# IB_WIFI_V2.net
KiCad netlist of a schematic drawn in EAGLE
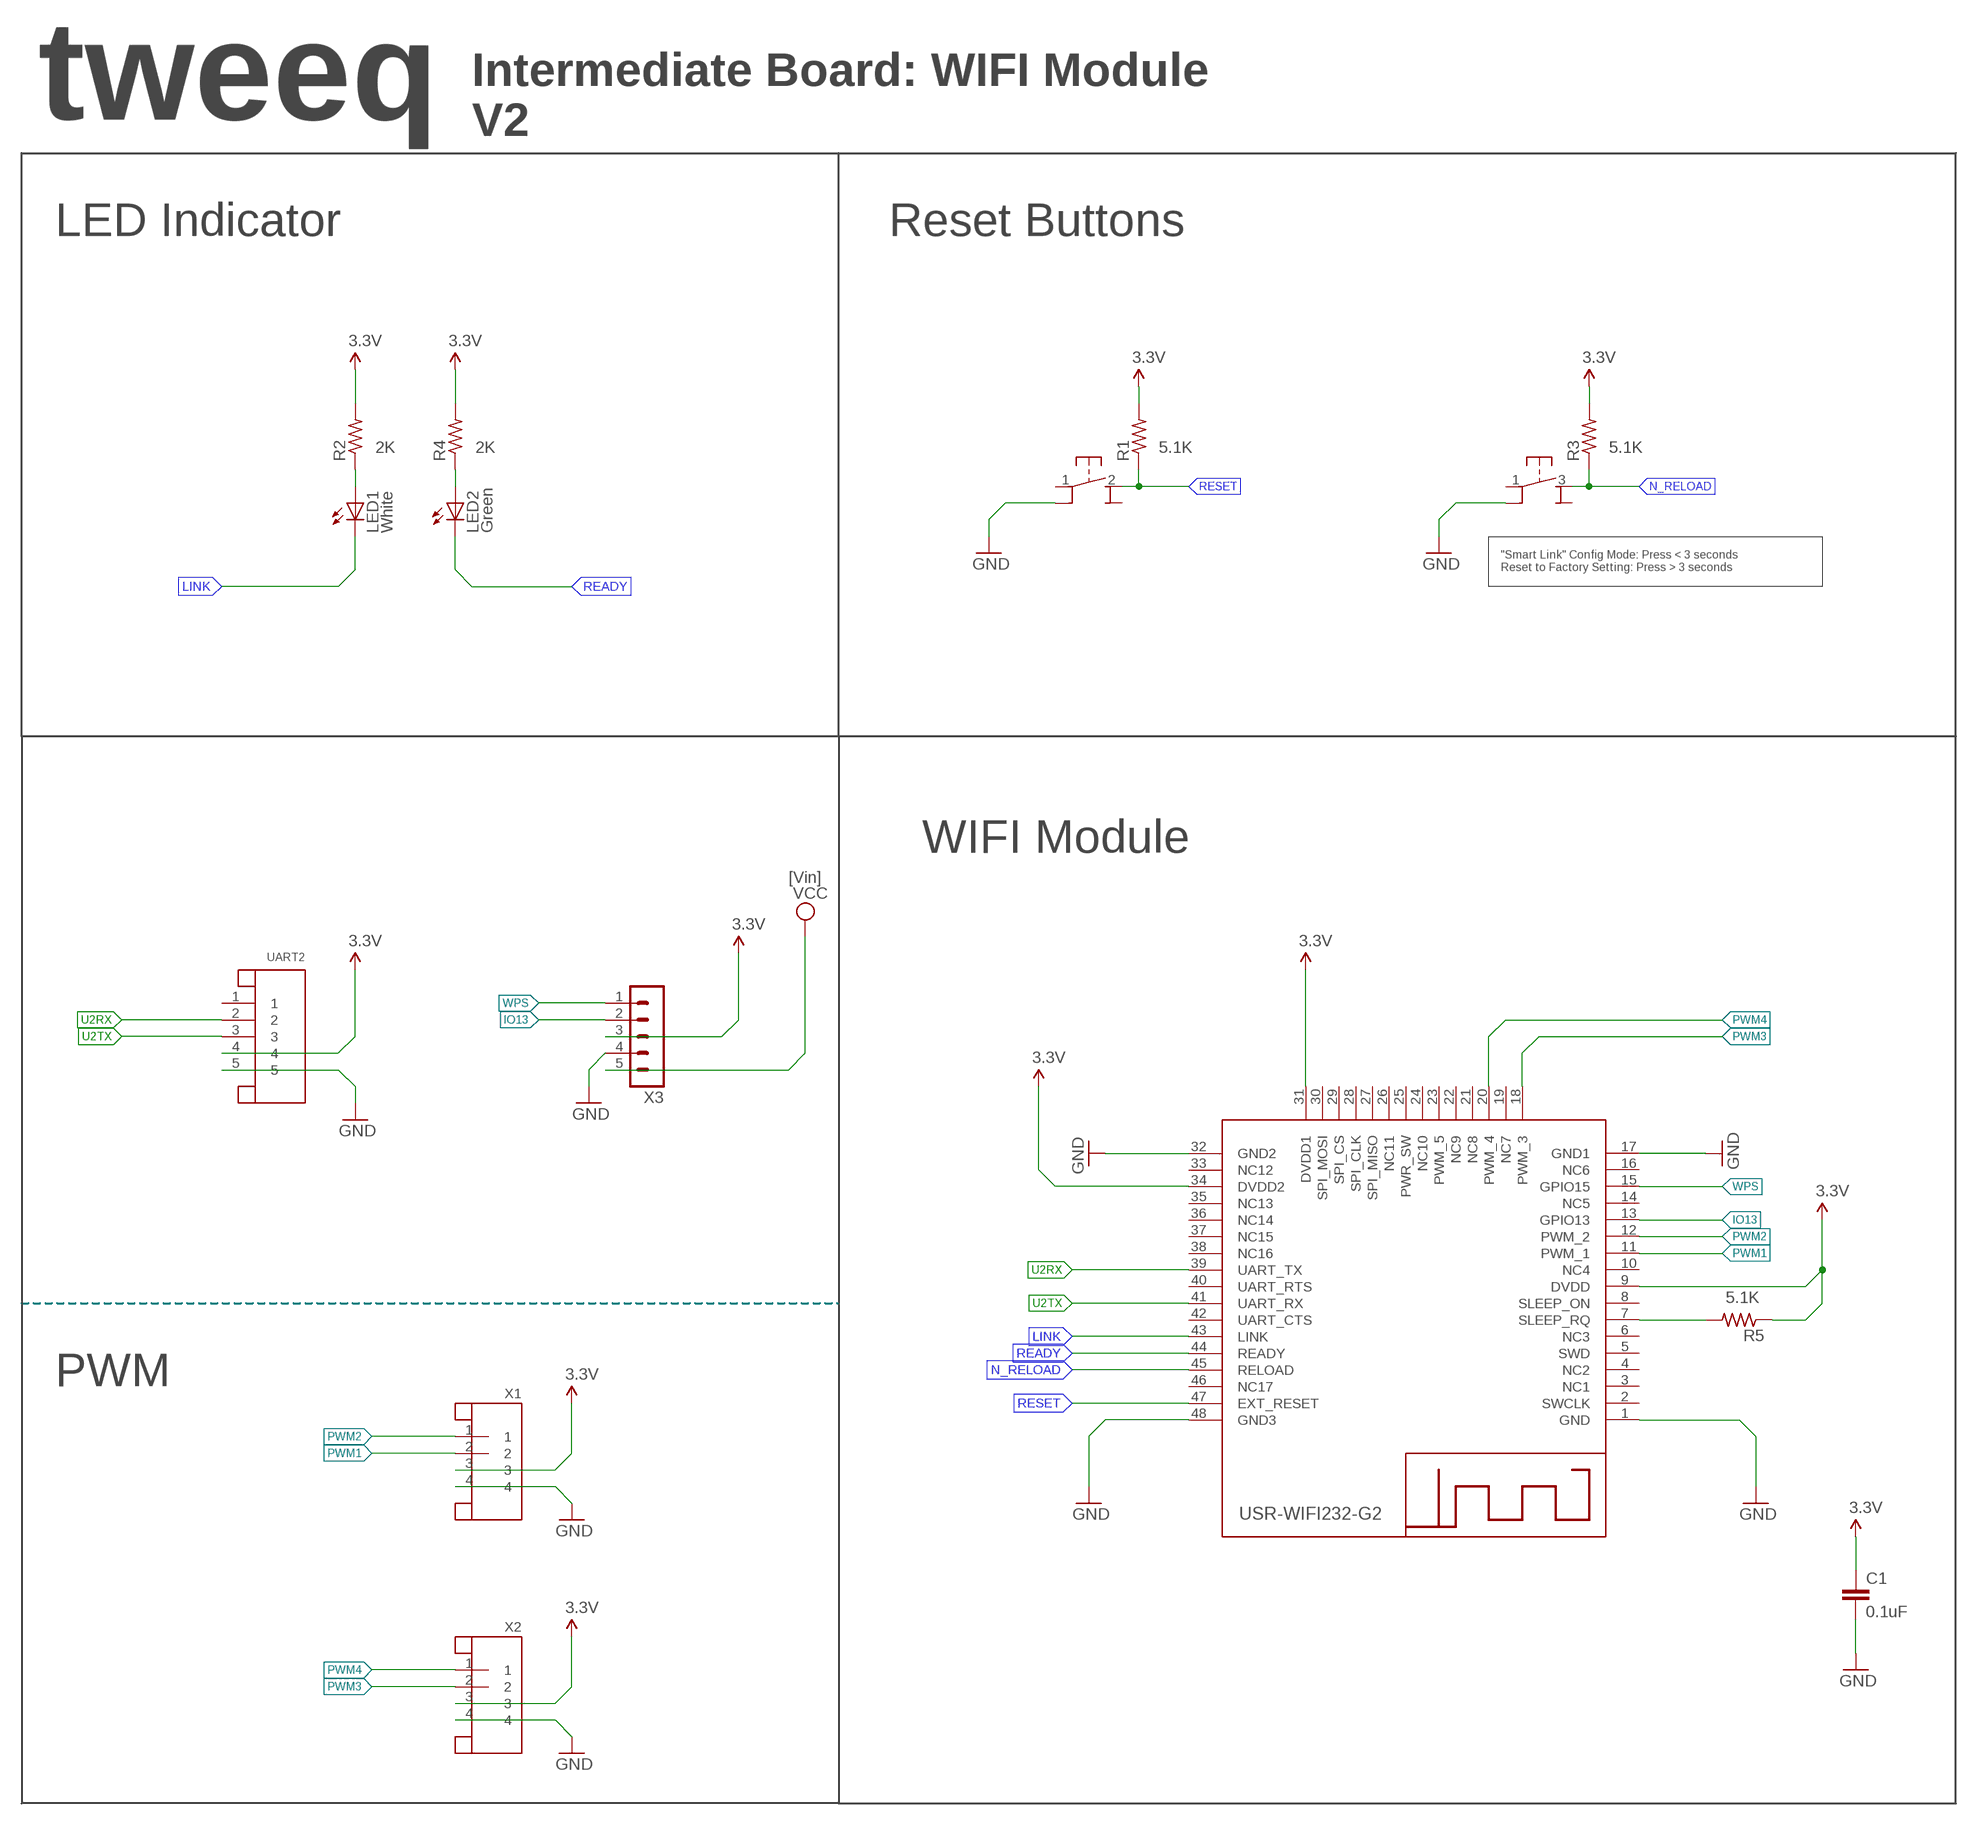
[diagram p0: schematic, sheet 1, part 1 of 2]
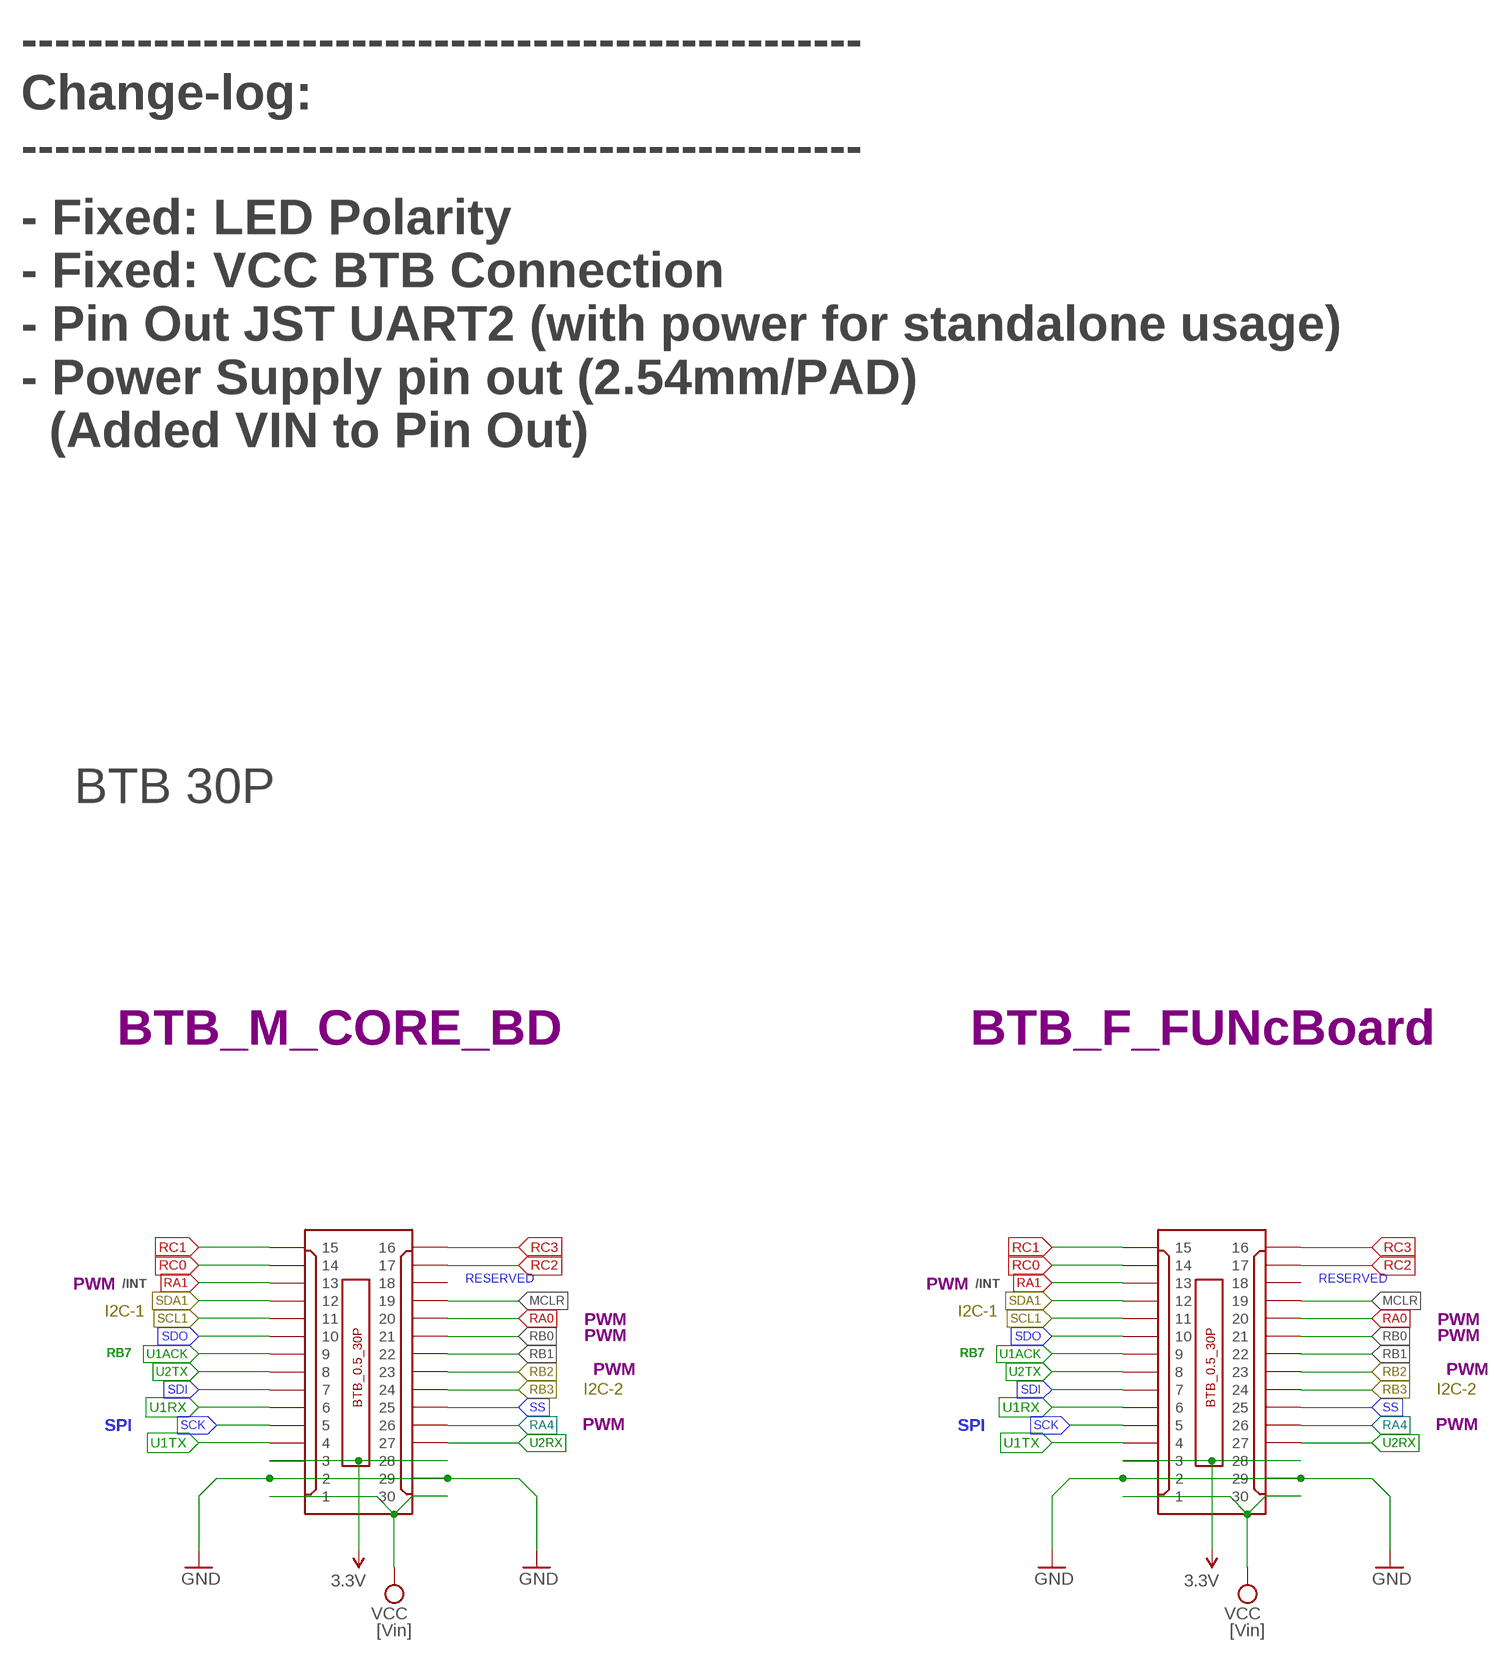
[diagram p1: schematic, sheet 1, part 2 of 2]

(export (version "E")
  (design (tool "Eeschema 10.0.6"))
  (components
    (comp (ref "C1")
      (value "0.1uF")
      (footprint "eagle-import:C0603")
      (libsource (lib "eagle-import") (part "C-EUC0603"))
    )
    (comp (ref "LED1")
      (value "White")
      (footprint "eagle-import:CHIPLED_0805")
      (libsource (lib "eagle-import") (part "LEDCHIPLED_0805"))
    )
    (comp (ref "LED2")
      (value "Green")
      (footprint "eagle-import:CHIPLED_0805")
      (libsource (lib "eagle-import") (part "LEDCHIPLED_0805"))
    )
    (comp (ref "R1")
      (value "5.1K")
      (footprint "eagle-import:R0603")
      (libsource (lib "eagle-import") (part "R-US_R0603"))
    )
    (comp (ref "R2")
      (value "2K")
      (footprint "eagle-import:R0603")
      (libsource (lib "eagle-import") (part "R-US_R0603"))
    )
    (comp (ref "R3")
      (value "5.1K")
      (footprint "eagle-import:R0603")
      (libsource (lib "eagle-import") (part "R-US_R0603"))
    )
    (comp (ref "R4")
      (value "2K")
      (footprint "eagle-import:R0603")
      (libsource (lib "eagle-import") (part "R-US_R0603"))
    )
    (comp (ref "R5")
      (value "5.1K")
      (footprint "eagle-import:R0603")
      (libsource (lib "eagle-import") (part "R-US_R0603"))
    )
    (comp (ref "U$1")
      (value "BTB_CONN_30P/M")
      (footprint "eagle-import:BTB0.5-30M-3.0G")
      (libsource (lib "eagle-import") (part "BTB_CONN_30P/M"))
    )
    (comp (ref "U$3")
      (value "BTB_CONN_30P/F")
      (footprint "eagle-import:BTB0.5-30F-3.0G")
      (libsource (lib "eagle-import") (part "BTB_CONN_30P/F"))
    )
    (comp (ref "U$4")
      (value "PB_MICRO_SMT")
      (footprint "eagle-import:PB_SMT_3.5X3X2")
      (libsource (lib "eagle-import") (part "PB_MICRO_SMT"))
    )
    (comp (ref "U$5")
      (value "PB_MICRO_SMTRIGHTANGLE")
      (footprint "eagle-import:PB_SMT_90D6.2X4.6")
      (libsource (lib "eagle-import") (part "PB_MICRO_SMTRIGHTANGLE"))
    )
    (comp (ref "UART2")
      (value "JST-5PINSH")
      (footprint "eagle-import:SH1.0-5PIN")
      (libsource (lib "eagle-import") (part "JST-5PINSH"))
    )
    (comp (ref "USR-WIFI232-G2")
      (value "USR-WIFI232-G2")
      (footprint "eagle-import:USR-WIFI232-G")
      (libsource (lib "eagle-import") (part "USR-WIFI232-G2"))
    )
    (comp (ref "X1")
      (value "JST-4PINSH")
      (footprint "eagle-import:SH1.0-4PIN")
      (libsource (lib "eagle-import") (part "JST-4PINSH"))
    )
    (comp (ref "X2")
      (value "JST-4PINSH")
      (footprint "eagle-import:SH1.0-4PIN")
      (libsource (lib "eagle-import") (part "JST-4PINSH"))
    )
    (comp (ref "X3")
      (value "M05-1PAD")
      (footprint "eagle-import:1X05_PAD")
      (libsource (lib "eagle-import") (part "M05-1PAD"))
    )
  )
  (nets
    (net (code "1") (name "3.3V") (class "Default")
      (node (ref "C1") (pin "1") (pinfunction "1_1") (pintype "passive"))
      (node (ref "R1") (pin "2") (pinfunction "2_2") (pintype "passive"))
      (node (ref "R2") (pin "2") (pinfunction "2_2") (pintype "passive"))
      (node (ref "R3") (pin "2") (pinfunction "2_2") (pintype "passive"))
      (node (ref "R4") (pin "2") (pinfunction "2_2") (pintype "passive"))
      (node (ref "R5") (pin "1") (pinfunction "1_1") (pintype "passive"))
      (node (ref "U$1") (pin "28") (pinfunction "28_28") (pintype "bidirectional"))
      (node (ref "U$1") (pin "3") (pinfunction "3_3") (pintype "bidirectional"))
      (node (ref "U$3") (pin "28") (pinfunction "28_28") (pintype "bidirectional"))
      (node (ref "U$3") (pin "3") (pinfunction "3_3") (pintype "bidirectional"))
      (node (ref "UART2") (pin "4") (pinfunction "4_4") (pintype "bidirectional"))
      (node (ref "USR-WIFI232-G2") (pin "31") (pinfunction "DVDD1_31") (pintype "bidirectional"))
      (node (ref "USR-WIFI232-G2") (pin "34") (pinfunction "DVDD2_34") (pintype "bidirectional"))
      (node (ref "USR-WIFI232-G2") (pin "9") (pinfunction "DVDD_9") (pintype "bidirectional"))
      (node (ref "X1") (pin "3") (pinfunction "3_3") (pintype "bidirectional"))
      (node (ref "X2") (pin "3") (pinfunction "3_3") (pintype "bidirectional"))
      (node (ref "X3") (pin "3") (pinfunction "3_3") (pintype "passive"))
    )
    (net (code "2") (name "GND") (class "Default")
      (node (ref "C1") (pin "2") (pinfunction "2_2") (pintype "passive"))
      (node (ref "U$1") (pin "2") (pinfunction "2_2") (pintype "bidirectional"))
      (node (ref "U$1") (pin "29") (pinfunction "29_29") (pintype "bidirectional"))
      (node (ref "U$3") (pin "2") (pinfunction "2_2") (pintype "bidirectional"))
      (node (ref "U$3") (pin "29") (pinfunction "29_29") (pintype "bidirectional"))
      (node (ref "U$4") (pin "2") (pinfunction "1A_2") (pintype "passive"))
      (node (ref "U$5") (pin "1A") (pinfunction "1A_1A") (pintype "passive"))
      (node (ref "UART2") (pin "5") (pinfunction "5_5") (pintype "bidirectional"))
      (node (ref "USR-WIFI232-G2") (pin "1") (pinfunction "GND_1") (pintype "bidirectional"))
      (node (ref "USR-WIFI232-G2") (pin "17") (pinfunction "GND1_17") (pintype "bidirectional"))
      (node (ref "USR-WIFI232-G2") (pin "32") (pinfunction "GND2_32") (pintype "bidirectional"))
      (node (ref "USR-WIFI232-G2") (pin "48") (pinfunction "GND3_48") (pintype "bidirectional"))
      (node (ref "X1") (pin "4") (pinfunction "4_4") (pintype "bidirectional"))
      (node (ref "X2") (pin "4") (pinfunction "4_4") (pintype "bidirectional"))
      (node (ref "X3") (pin "4") (pinfunction "4_4") (pintype "passive"))
    )
    (net (code "3") (name "IO13") (class "Default")
      (node (ref "USR-WIFI232-G2") (pin "13") (pinfunction "GPIO13_13") (pintype "bidirectional"))
      (node (ref "X3") (pin "2") (pinfunction "2_2") (pintype "passive"))
    )
    (net (code "4") (name "LINK") (class "Default")
      (node (ref "LED1") (pin "C") (pinfunction "C_C") (pintype "passive"))
      (node (ref "USR-WIFI232-G2") (pin "43") (pinfunction "LINK_43") (pintype "bidirectional"))
    )
    (net (code "5") (name "MCLR") (class "Default")
      (node (ref "U$1") (pin "19") (pinfunction "19_19") (pintype "bidirectional"))
      (node (ref "U$3") (pin "19") (pinfunction "19_19") (pintype "bidirectional"))
    )
    (net (code "6") (name "N_RELOAD") (class "Default")
      (node (ref "R3") (pin "1") (pinfunction "1_1") (pintype "passive"))
      (node (ref "U$4") (pin "3") (pinfunction "2_3") (pintype "passive"))
      (node (ref "USR-WIFI232-G2") (pin "45") (pinfunction "RELOAD_45") (pintype "bidirectional"))
    )
    (net (code "7") (name "Net-(LED1-PadA)") (class "Default")
      (node (ref "LED1") (pin "A") (pinfunction "A_A") (pintype "passive"))
      (node (ref "R2") (pin "1") (pinfunction "1_1") (pintype "passive"))
    )
    (net (code "8") (name "Net-(LED2-PadA)") (class "Default")
      (node (ref "LED2") (pin "A") (pinfunction "A_A") (pintype "passive"))
      (node (ref "R4") (pin "1") (pinfunction "1_1") (pintype "passive"))
    )
    (net (code "9") (name "Net-(USR-WIFI232-G2-SLEEP_RQ)") (class "Default")
      (node (ref "R5") (pin "2") (pinfunction "2_2") (pintype "passive"))
      (node (ref "USR-WIFI232-G2") (pin "7") (pinfunction "SLEEP_RQ_7") (pintype "bidirectional"))
    )
    (net (code "10") (name "PWM1") (class "Default")
      (node (ref "USR-WIFI232-G2") (pin "11") (pinfunction "PWM_1_11") (pintype "bidirectional"))
      (node (ref "X1") (pin "2") (pinfunction "2_2") (pintype "bidirectional"))
    )
    (net (code "11") (name "PWM2") (class "Default")
      (node (ref "USR-WIFI232-G2") (pin "12") (pinfunction "PWM_2_12") (pintype "bidirectional"))
      (node (ref "X1") (pin "1") (pinfunction "1_1") (pintype "bidirectional"))
    )
    (net (code "12") (name "PWM3") (class "Default")
      (node (ref "USR-WIFI232-G2") (pin "18") (pinfunction "PWM_3_18") (pintype "bidirectional"))
      (node (ref "X2") (pin "2") (pinfunction "2_2") (pintype "bidirectional"))
    )
    (net (code "13") (name "PWM4") (class "Default")
      (node (ref "USR-WIFI232-G2") (pin "20") (pinfunction "PWM_4_20") (pintype "bidirectional"))
      (node (ref "X2") (pin "1") (pinfunction "1_1") (pintype "bidirectional"))
    )
    (net (code "14") (name "RA0") (class "Default")
      (node (ref "U$1") (pin "20") (pinfunction "20_20") (pintype "bidirectional"))
      (node (ref "U$3") (pin "20") (pinfunction "20_20") (pintype "bidirectional"))
    )
    (net (code "15") (name "RA1") (class "Default")
      (node (ref "U$1") (pin "13") (pinfunction "13_13") (pintype "bidirectional"))
      (node (ref "U$3") (pin "13") (pinfunction "13_13") (pintype "bidirectional"))
    )
    (net (code "16") (name "RA4") (class "Default")
      (node (ref "U$1") (pin "26") (pinfunction "26_26") (pintype "bidirectional"))
      (node (ref "U$3") (pin "26") (pinfunction "26_26") (pintype "bidirectional"))
    )
    (net (code "17") (name "RB0") (class "Default")
      (node (ref "U$1") (pin "21") (pinfunction "21_21") (pintype "bidirectional"))
      (node (ref "U$3") (pin "21") (pinfunction "21_21") (pintype "bidirectional"))
    )
    (net (code "18") (name "RB1") (class "Default")
      (node (ref "U$1") (pin "22") (pinfunction "22_22") (pintype "bidirectional"))
      (node (ref "U$3") (pin "22") (pinfunction "22_22") (pintype "bidirectional"))
    )
    (net (code "19") (name "RB2") (class "Default")
      (node (ref "U$1") (pin "23") (pinfunction "23_23") (pintype "bidirectional"))
      (node (ref "U$3") (pin "23") (pinfunction "23_23") (pintype "bidirectional"))
    )
    (net (code "20") (name "RB3") (class "Default")
      (node (ref "U$1") (pin "24") (pinfunction "24_24") (pintype "bidirectional"))
      (node (ref "U$3") (pin "24") (pinfunction "24_24") (pintype "bidirectional"))
    )
    (net (code "21") (name "RC0") (class "Default")
      (node (ref "U$1") (pin "14") (pinfunction "14_14") (pintype "bidirectional"))
      (node (ref "U$3") (pin "14") (pinfunction "14_14") (pintype "bidirectional"))
    )
    (net (code "22") (name "RC1") (class "Default")
      (node (ref "U$1") (pin "15") (pinfunction "15_15") (pintype "bidirectional"))
      (node (ref "U$3") (pin "15") (pinfunction "15_15") (pintype "bidirectional"))
    )
    (net (code "23") (name "RC2") (class "Default")
      (node (ref "U$1") (pin "17") (pinfunction "17_17") (pintype "bidirectional"))
      (node (ref "U$3") (pin "17") (pinfunction "17_17") (pintype "bidirectional"))
    )
    (net (code "24") (name "RC3") (class "Default")
      (node (ref "U$1") (pin "16") (pinfunction "16_16") (pintype "bidirectional"))
      (node (ref "U$3") (pin "16") (pinfunction "16_16") (pintype "bidirectional"))
    )
    (net (code "25") (name "READY") (class "Default")
      (node (ref "LED2") (pin "C") (pinfunction "C_C") (pintype "passive"))
      (node (ref "USR-WIFI232-G2") (pin "44") (pinfunction "READY_44") (pintype "bidirectional"))
    )
    (net (code "26") (name "RESET") (class "Default")
      (node (ref "R1") (pin "1") (pinfunction "1_1") (pintype "passive"))
      (node (ref "U$5") (pin "2") (pinfunction "2_2") (pintype "passive"))
      (node (ref "USR-WIFI232-G2") (pin "47") (pinfunction "EXT_RESET_47") (pintype "bidirectional"))
    )
    (net (code "27") (name "SCK") (class "Default")
      (node (ref "U$1") (pin "5") (pinfunction "5_5") (pintype "bidirectional"))
      (node (ref "U$3") (pin "5") (pinfunction "5_5") (pintype "bidirectional"))
    )
    (net (code "28") (name "SCL1") (class "Default")
      (node (ref "U$1") (pin "11") (pinfunction "11_11") (pintype "bidirectional"))
      (node (ref "U$3") (pin "11") (pinfunction "11_11") (pintype "bidirectional"))
    )
    (net (code "29") (name "SDA1") (class "Default")
      (node (ref "U$1") (pin "12") (pinfunction "12_12") (pintype "bidirectional"))
      (node (ref "U$3") (pin "12") (pinfunction "12_12") (pintype "bidirectional"))
    )
    (net (code "30") (name "SDI") (class "Default")
      (node (ref "U$1") (pin "7") (pinfunction "7_7") (pintype "bidirectional"))
      (node (ref "U$3") (pin "7") (pinfunction "7_7") (pintype "bidirectional"))
    )
    (net (code "31") (name "SDO") (class "Default")
      (node (ref "U$1") (pin "10") (pinfunction "10_10") (pintype "bidirectional"))
      (node (ref "U$3") (pin "10") (pinfunction "10_10") (pintype "bidirectional"))
    )
    (net (code "32") (name "SS") (class "Default")
      (node (ref "U$1") (pin "25") (pinfunction "25_25") (pintype "bidirectional"))
      (node (ref "U$3") (pin "25") (pinfunction "25_25") (pintype "bidirectional"))
    )
    (net (code "33") (name "U1ACK") (class "Default")
      (node (ref "U$1") (pin "9") (pinfunction "9_9") (pintype "bidirectional"))
      (node (ref "U$3") (pin "9") (pinfunction "9_9") (pintype "bidirectional"))
    )
    (net (code "34") (name "U1RX") (class "Default")
      (node (ref "U$1") (pin "6") (pinfunction "6_6") (pintype "bidirectional"))
      (node (ref "U$3") (pin "6") (pinfunction "6_6") (pintype "bidirectional"))
    )
    (net (code "35") (name "U1TX") (class "Default")
      (node (ref "U$1") (pin "4") (pinfunction "4_4") (pintype "bidirectional"))
      (node (ref "U$3") (pin "4") (pinfunction "4_4") (pintype "bidirectional"))
    )
    (net (code "36") (name "U2RX") (class "Default")
      (node (ref "U$1") (pin "27") (pinfunction "27_27") (pintype "bidirectional"))
      (node (ref "U$3") (pin "27") (pinfunction "27_27") (pintype "bidirectional"))
      (node (ref "UART2") (pin "2") (pinfunction "2_2") (pintype "bidirectional"))
      (node (ref "USR-WIFI232-G2") (pin "39") (pinfunction "UART_TX_39") (pintype "bidirectional"))
    )
    (net (code "37") (name "U2TX") (class "Default")
      (node (ref "U$1") (pin "8") (pinfunction "8_8") (pintype "bidirectional"))
      (node (ref "U$3") (pin "8") (pinfunction "8_8") (pintype "bidirectional"))
      (node (ref "UART2") (pin "3") (pinfunction "3_3") (pintype "bidirectional"))
      (node (ref "USR-WIFI232-G2") (pin "41") (pinfunction "UART_RX_41") (pintype "bidirectional"))
    )
    (net (code "38") (name "VCC") (class "Default")
      (node (ref "U$1") (pin "1") (pinfunction "1_1") (pintype "bidirectional"))
      (node (ref "U$1") (pin "30") (pinfunction "30_30") (pintype "bidirectional"))
      (node (ref "U$3") (pin "1") (pinfunction "1_1") (pintype "bidirectional"))
      (node (ref "U$3") (pin "30") (pinfunction "30_30") (pintype "bidirectional"))
      (node (ref "X3") (pin "5") (pinfunction "5_5") (pintype "passive"))
    )
    (net (code "39") (name "WPS") (class "Default")
      (node (ref "USR-WIFI232-G2") (pin "15") (pinfunction "GPIO15_15") (pintype "bidirectional"))
      (node (ref "X3") (pin "1") (pinfunction "1_1") (pintype "passive"))
    )
    (net (code "40") (name "unconnected-(U$1-Pad18)") (class "Default")
      (node (ref "U$1") (pin "18") (pinfunction "18_18") (pintype "bidirectional"))
    )
    (net (code "41") (name "unconnected-(U$3-Pad18)") (class "Default")
      (node (ref "U$3") (pin "18") (pinfunction "18_18") (pintype "bidirectional"))
    )
    (net (code "42") (name "unconnected-(U$4-2A-Pad4)") (class "Default")
      (node (ref "U$4") (pin "4") (pinfunction "2A_4") (pintype "passive"))
    )
    (net (code "43") (name "unconnected-(U$4-Pad1)") (class "Default")
      (node (ref "U$4") (pin "1") (pinfunction "1_1") (pintype "passive"))
    )
    (net (code "44") (name "unconnected-(U$5-Pad1)") (class "Default")
      (node (ref "U$5") (pin "1") (pinfunction "1_1") (pintype "passive"))
    )
    (net (code "45") (name "unconnected-(U$5-Pad2A)") (class "Default")
      (node (ref "U$5") (pin "2A") (pinfunction "2A_2A") (pintype "passive"))
    )
    (net (code "46") (name "unconnected-(UART2-Pad1)") (class "Default")
      (node (ref "UART2") (pin "1") (pinfunction "1_1") (pintype "bidirectional"))
    )
    (net (code "47") (name "unconnected-(USR-WIFI232-G2-NC1-Pad3)") (class "Default")
      (node (ref "USR-WIFI232-G2") (pin "3") (pinfunction "NC1_3") (pintype "no_connect"))
    )
    (net (code "48") (name "unconnected-(USR-WIFI232-G2-NC2-Pad4)") (class "Default")
      (node (ref "USR-WIFI232-G2") (pin "4") (pinfunction "NC2_4") (pintype "no_connect"))
    )
    (net (code "49") (name "unconnected-(USR-WIFI232-G2-NC3-Pad6)") (class "Default")
      (node (ref "USR-WIFI232-G2") (pin "6") (pinfunction "NC3_6") (pintype "no_connect"))
    )
    (net (code "50") (name "unconnected-(USR-WIFI232-G2-NC4-Pad10)") (class "Default")
      (node (ref "USR-WIFI232-G2") (pin "10") (pinfunction "NC4_10") (pintype "no_connect"))
    )
    (net (code "51") (name "unconnected-(USR-WIFI232-G2-NC5-Pad14)") (class "Default")
      (node (ref "USR-WIFI232-G2") (pin "14") (pinfunction "NC5_14") (pintype "no_connect"))
    )
    (net (code "52") (name "unconnected-(USR-WIFI232-G2-NC6-Pad16)") (class "Default")
      (node (ref "USR-WIFI232-G2") (pin "16") (pinfunction "NC6_16") (pintype "no_connect"))
    )
    (net (code "53") (name "unconnected-(USR-WIFI232-G2-NC7-Pad19)") (class "Default")
      (node (ref "USR-WIFI232-G2") (pin "19") (pinfunction "NC7_19") (pintype "no_connect"))
    )
    (net (code "54") (name "unconnected-(USR-WIFI232-G2-NC8-Pad21)") (class "Default")
      (node (ref "USR-WIFI232-G2") (pin "21") (pinfunction "NC8_21") (pintype "no_connect"))
    )
    (net (code "55") (name "unconnected-(USR-WIFI232-G2-NC9-Pad22)") (class "Default")
      (node (ref "USR-WIFI232-G2") (pin "22") (pinfunction "NC9_22") (pintype "no_connect"))
    )
    (net (code "56") (name "unconnected-(USR-WIFI232-G2-NC10-Pad24)") (class "Default")
      (node (ref "USR-WIFI232-G2") (pin "24") (pinfunction "NC10_24") (pintype "no_connect"))
    )
    (net (code "57") (name "unconnected-(USR-WIFI232-G2-NC11-Pad26)") (class "Default")
      (node (ref "USR-WIFI232-G2") (pin "26") (pinfunction "NC11_26") (pintype "no_connect"))
    )
    (net (code "58") (name "unconnected-(USR-WIFI232-G2-NC12-Pad33)") (class "Default")
      (node (ref "USR-WIFI232-G2") (pin "33") (pinfunction "NC12_33") (pintype "bidirectional"))
    )
    (net (code "59") (name "unconnected-(USR-WIFI232-G2-NC13-Pad35)") (class "Default")
      (node (ref "USR-WIFI232-G2") (pin "35") (pinfunction "NC13_35") (pintype "no_connect"))
    )
    (net (code "60") (name "unconnected-(USR-WIFI232-G2-NC14-Pad36)") (class "Default")
      (node (ref "USR-WIFI232-G2") (pin "36") (pinfunction "NC14_36") (pintype "no_connect"))
    )
    (net (code "61") (name "unconnected-(USR-WIFI232-G2-NC15-Pad37)") (class "Default")
      (node (ref "USR-WIFI232-G2") (pin "37") (pinfunction "NC15_37") (pintype "no_connect"))
    )
    (net (code "62") (name "unconnected-(USR-WIFI232-G2-NC16-Pad38)") (class "Default")
      (node (ref "USR-WIFI232-G2") (pin "38") (pinfunction "NC16_38") (pintype "no_connect"))
    )
    (net (code "63") (name "unconnected-(USR-WIFI232-G2-NC17-Pad46)") (class "Default")
      (node (ref "USR-WIFI232-G2") (pin "46") (pinfunction "NC17_46") (pintype "no_connect"))
    )
    (net (code "64") (name "unconnected-(USR-WIFI232-G2-PWM_5-Pad23)") (class "Default")
      (node (ref "USR-WIFI232-G2") (pin "23") (pinfunction "PWM_5_23") (pintype "bidirectional"))
    )
    (net (code "65") (name "unconnected-(USR-WIFI232-G2-PWR_SW-Pad25)") (class "Default")
      (node (ref "USR-WIFI232-G2") (pin "25") (pinfunction "PWR_SW_25") (pintype "bidirectional"))
    )
    (net (code "66") (name "unconnected-(USR-WIFI232-G2-SLEEP_ON-Pad8)") (class "Default")
      (node (ref "USR-WIFI232-G2") (pin "8") (pinfunction "SLEEP_ON_8") (pintype "bidirectional"))
    )
    (net (code "67") (name "unconnected-(USR-WIFI232-G2-SPI_CLK-Pad28)") (class "Default")
      (node (ref "USR-WIFI232-G2") (pin "28") (pinfunction "SPI_CLK_28") (pintype "bidirectional"))
    )
    (net (code "68") (name "unconnected-(USR-WIFI232-G2-SPI_CS-Pad29)") (class "Default")
      (node (ref "USR-WIFI232-G2") (pin "29") (pinfunction "SPI_CS_29") (pintype "bidirectional"))
    )
    (net (code "69") (name "unconnected-(USR-WIFI232-G2-SPI_MISO-Pad27)") (class "Default")
      (node (ref "USR-WIFI232-G2") (pin "27") (pinfunction "SPI_MISO_27") (pintype "bidirectional"))
    )
    (net (code "70") (name "unconnected-(USR-WIFI232-G2-SPI_MOSI-Pad30)") (class "Default")
      (node (ref "USR-WIFI232-G2") (pin "30") (pinfunction "SPI_MOSI_30") (pintype "bidirectional"))
    )
    (net (code "71") (name "unconnected-(USR-WIFI232-G2-SWCLK-Pad2)") (class "Default")
      (node (ref "USR-WIFI232-G2") (pin "2") (pinfunction "SWCLK_2") (pintype "bidirectional"))
    )
    (net (code "72") (name "unconnected-(USR-WIFI232-G2-SWD-Pad5)") (class "Default")
      (node (ref "USR-WIFI232-G2") (pin "5") (pinfunction "SWD_5") (pintype "bidirectional"))
    )
    (net (code "73") (name "unconnected-(USR-WIFI232-G2-UART_CTS-Pad42)") (class "Default")
      (node (ref "USR-WIFI232-G2") (pin "42") (pinfunction "UART_CTS_42") (pintype "bidirectional"))
    )
    (net (code "74") (name "unconnected-(USR-WIFI232-G2-UART_RTS-Pad40)") (class "Default")
      (node (ref "USR-WIFI232-G2") (pin "40") (pinfunction "UART_RTS_40") (pintype "bidirectional"))
    )
  )
)
